# Key.net
KiCad netlist of a schematic drawn in Altium Designer
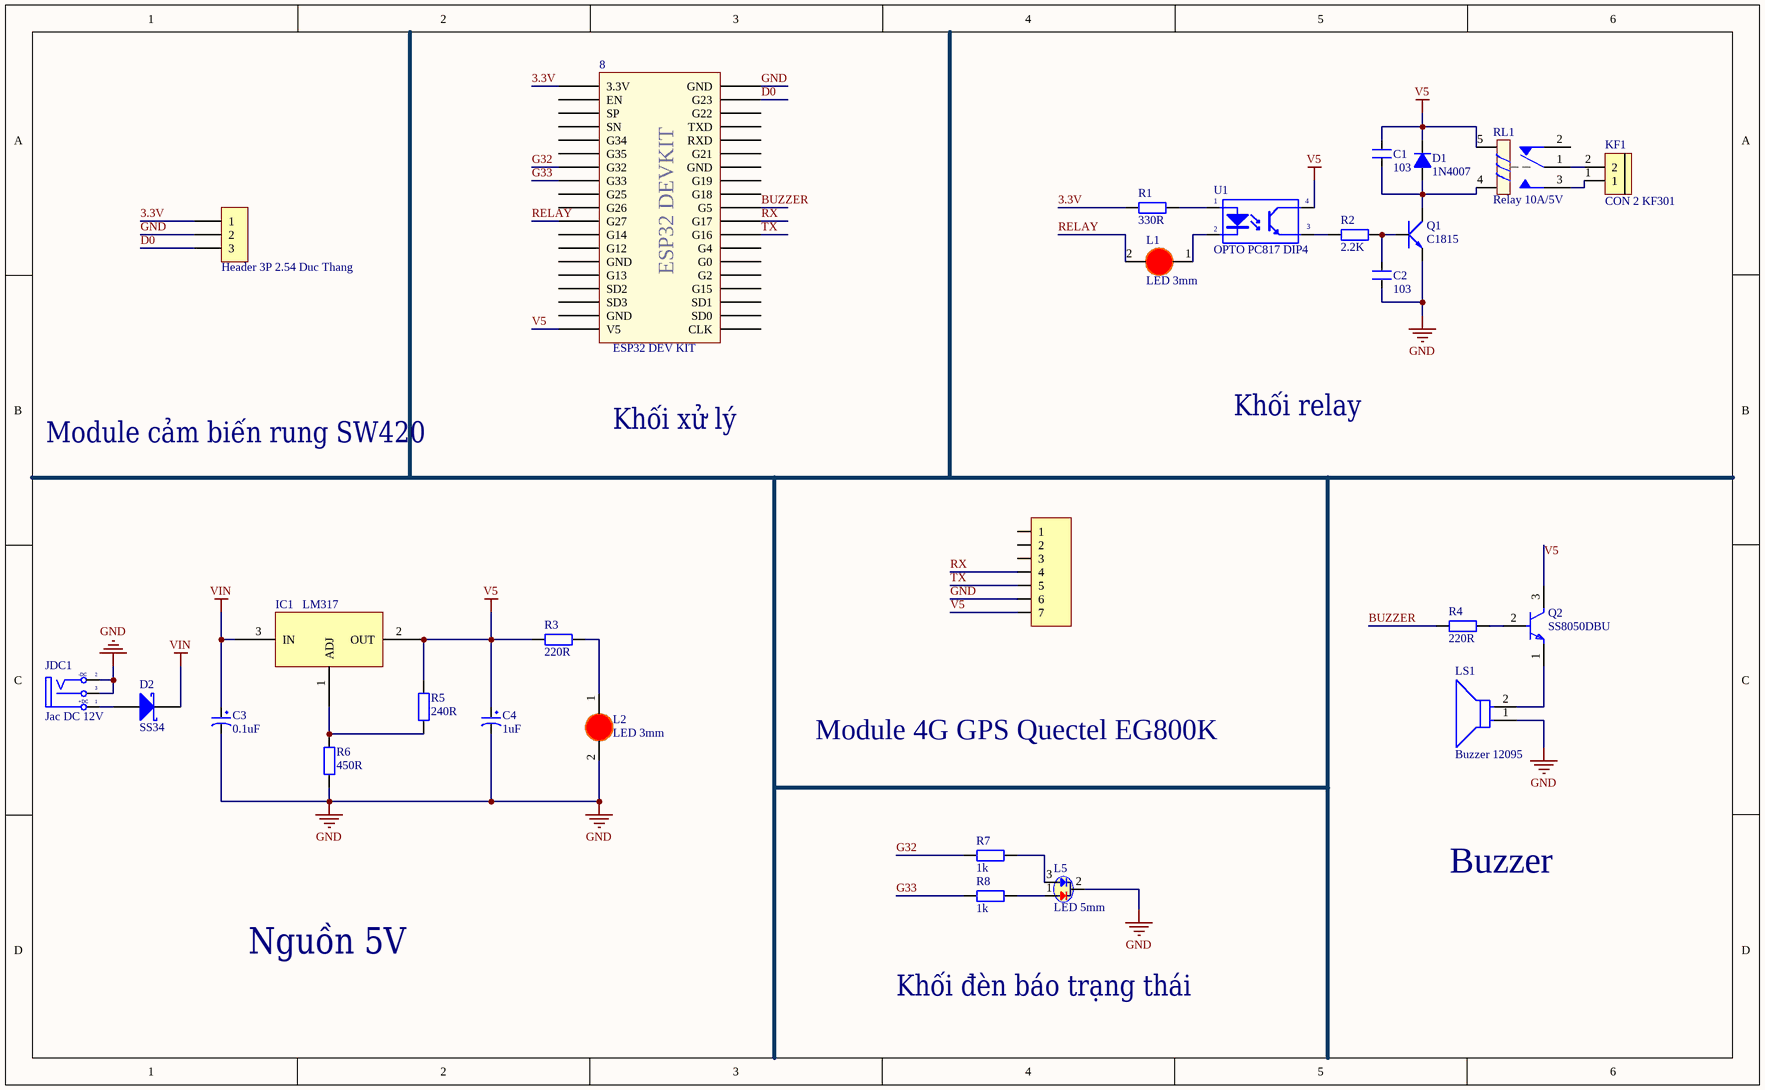
[diagram p0: Key.SchDoc]

(export (version "E")
  (design (tool "Eeschema 10.0.6"))
  (components
    (comp (ref "8")
      (value "ESP32 DEV KIT")
      (footprint "ESP32 DEVKIT")
      (libsource (lib "Altium_Lib_by_KhueNguyenCreator") (part "ESP32 DEV KIT"))
    )
    (comp (ref "C1")
      (value "103")
      (footprint "CN1.5")
      (description "Cap np 682pF => 104pF")
      (libsource (lib "syhaunguyen") (part "CN1.5"))
    )
    (comp (ref "C2")
      (value "103")
      (footprint "CN1.5")
      (description "Cap np 682pF => 104pF")
      (libsource (lib "syhaunguyen") (part "CN1.5"))
    )
    (comp (ref "C3")
      (value "0.1uF")
      (footprint "CP1/2")
      (description "Cap P  0,1uF < 22uF , 16 - 50V")
      (libsource (lib "syhaunguyen") (part "CP1"))
    )
    (comp (ref "C4")
      (value "1uF")
      (footprint "CP1/2")
      (description "Cap P  0,1uF < 22uF , 16 - 50V")
      (libsource (lib "syhaunguyen") (part "CP1"))
    )
    (comp (ref "D1")
      (value "1N4007")
      (footprint "DIODE 1A")
      (description "Cắm")
      (libsource (lib "Altium_Lib_by_KhueNguyenCreator") (part "Diode 1N4007"))
    )
    (comp (ref "D2")
      (value "SS34")
      (footprint "SS14")
      (description "Schottky Diode")
      (fields (field (name "PUBLISHER") "Altium Limited"))
      (libsource (lib "Miscellaneous Devices") (part "D Schottky"))
    )
    (comp (ref "H1")
      (value "Header 3P 2.54 Duc Thang")
      (footprint "XH2.54M-3")
      (description "Cắm")
      (libsource (lib "Altium_Lib_by_KhueNguyenCreator") (part "Header 3P 2.54 Duc Thang"))
    )
    (comp (ref "IC1")
      (value "LM317")
      (footprint "SOT223")
      (description "Dán")
      (libsource (lib "IC") (part "LM317 TO223 SMD"))
    )
    (comp (ref "JDC1")
      (value "Jac DC 12V")
      (footprint "DC-IN")
      (description "Jac DC input")
      (libsource (lib "syhaunguyen") (part "DCIN"))
    )
    (comp (ref "JP2")
      (value "~")
      (footprint "JP 1x7 CT")
      (description "Cắm")
      (libsource (lib "Altium_Lib_by_KhueNguyenCreator") (part "JP 1x7 2.54 Cai Thang"))
    )
    (comp (ref "KF1")
      (value "CON 2 KF301")
      (footprint "Con 2 KF301 5.08")
      (description "Cắm")
      (libsource (lib "Altium_Lib_by_KhueNguyenCreator") (part "CON 2 KF301"))
    )
    (comp (ref "L1")
      (value "LED 3mm")
      (footprint "LED-3MM-RED")
      (description "Cắm")
      (libsource (lib "Altium_Lib_by_KhueNguyenCreator") (part "LED 3mm Do"))
    )
    (comp (ref "L2")
      (value "LED 3mm")
      (footprint "LED-3MM-RED")
      (description "Cắm")
      (libsource (lib "Altium_Lib_by_KhueNguyenCreator") (part "LED 3mm Do"))
    )
    (comp (ref "L5")
      (value "LED 5mm")
      (footprint "LED-5MM 2 MAU")
      (description "Cắm")
      (libsource (lib "Altium_Lib_by_KhueNguyenCreator") (part "LED 5mm 2 mau Katot chung"))
    )
    (comp (ref "LS1")
      (value "Buzzer 12095")
      (footprint "FP-MCKPX-G1203A-K4056-MFG")
      (description "MAGNETIC BUZZER AND TRANSDUCER - More Details")
      (fields
        (field (name "MANUFACTURER PART NUMBER") "MCKPX-G1203A-K4056")
        (field (name "MANUFACTURER") "Multicomp Pro")
      )
      (libsource (lib "buzzer_pin7.6mm") (part "CMP-12433-000001-1"))
    )
    (comp (ref "Q1")
      (value "C1815")
      (footprint "TO92")
      (description "NPN transistor")
      (libsource (lib "Altium_Lib_by_KhueNguyenCreator") (part "Trans C1815 DIP"))
    )
    (comp (ref "Q2")
      (value "SS8050DBU")
      (footprint "FP-135AN-MFG")
      (description "SS8050DBU Bipolar (BJT) Single Transistor, NPN, 25 V, 100 MHz, 1 W, 1.5 A, 160")
      (libsource (lib "S8050_cam") (part "CMP-00278-84331634-1"))
    )
    (comp (ref "R1")
      (value "330R")
      (footprint "tro vach 1/4w")
      (description "Cắm")
      (libsource (lib "Altium_Lib_by_KhueNguyenCreator") (part "Tro Vach 1/4W 1% 330R"))
    )
    (comp (ref "R2")
      (value "2.2K")
      (footprint "tro vach 1/4w")
      (description "Cắm")
      (libsource (lib "Altium_Lib_by_KhueNguyenCreator") (part "Tro Vach 1/4W 5% 1k"))
    )
    (comp (ref "R3")
      (value "220R")
      (footprint "tro vach 1/4w")
      (description "Cắm")
      (libsource (lib "Altium_Lib_by_KhueNguyenCreator") (part "Tro Vach 1/4W 5% 220R"))
    )
    (comp (ref "R4")
      (value "220R")
      (footprint "tro vach 1/4w")
      (description "Cắm")
      (libsource (lib "Altium_Lib_by_KhueNguyenCreator") (part "Tro Vach 1/4W 5% 220R"))
    )
    (comp (ref "R5")
      (value "240R")
      (footprint "tro vach 1/4w")
      (description "Cắm")
      (libsource (lib "Altium_Lib_by_KhueNguyenCreator") (part "Tro Vach 1/4W 5% 220R"))
    )
    (comp (ref "R6")
      (value "450R")
      (footprint "tro vach 1/4w")
      (description "Cắm")
      (libsource (lib "Altium_Lib_by_KhueNguyenCreator") (part "Tro Vach 1/4W 5% 220R"))
    )
    (comp (ref "R7")
      (value "1k")
      (footprint "tro vach 1/4w")
      (description "Cắm")
      (libsource (lib "Altium_Lib_by_KhueNguyenCreator") (part "Tro Vach 1/4W 5% 220R"))
    )
    (comp (ref "R8")
      (value "1k")
      (footprint "tro vach 1/4w")
      (description "Cắm")
      (libsource (lib "Altium_Lib_by_KhueNguyenCreator") (part "Tro Vach 1/4W 5% 220R"))
    )
    (comp (ref "RL1")
      (value "Relay 10A/5V")
      (footprint "Relay 5 Chan SRD")
      (description "Relay 5 Chan")
      (libsource (lib "Altium_Lib_by_KhueNguyenCreator") (part "Relay 5 Chan SRD"))
    )
    (comp (ref "U1")
      (value "OPTO PC817 DIP4")
      (footprint "DIP4")
      (description "Single Opto")
      (libsource (lib "Altium_Lib_by_KhueNguyenCreator") (part "OPTO PC817 DIP4"))
    )
  )
  (nets
    (net (code "1") (name "/3.3V") (class "Default")
      (node (ref "8") (pin "1") (pinfunction "3.3V_1") (pintype "passive"))
      (node (ref "H1") (pin "1") (pinfunction "1_1") (pintype "passive"))
      (node (ref "R1") (pin "1") (pinfunction "1_1") (pintype "passive"))
    )
    (net (code "2") (name "/BUZZER") (class "Default")
      (node (ref "8") (pin "29") (pinfunction "G5_29") (pintype "passive"))
      (node (ref "R4") (pin "1") (pinfunction "1_1") (pintype "passive"))
    )
    (net (code "3") (name "/D0") (class "Default")
      (node (ref "8") (pin "37") (pinfunction "G23_37") (pintype "passive"))
      (node (ref "H1") (pin "3") (pinfunction "3_3") (pintype "passive"))
    )
    (net (code "4") (name "/G32") (class "Default")
      (node (ref "8") (pin "7") (pinfunction "G32_7") (pintype "passive"))
      (node (ref "R7") (pin "1") (pinfunction "1_1") (pintype "passive"))
    )
    (net (code "5") (name "/G33") (class "Default")
      (node (ref "8") (pin "8") (pinfunction "G33_8") (pintype "passive"))
      (node (ref "R8") (pin "1") (pinfunction "1_1") (pintype "passive"))
    )
    (net (code "6") (name "/RELAY") (class "Default")
      (node (ref "8") (pin "11") (pinfunction "G27_11") (pintype "passive"))
      (node (ref "L1") (pin "2") (pinfunction "K_2") (pintype "passive"))
    )
    (net (code "7") (name "/RX") (class "Default")
      (node (ref "8") (pin "28") (pinfunction "G17_28") (pintype "passive"))
      (node (ref "JP2") (pin "4") (pinfunction "4_4") (pintype "passive"))
    )
    (net (code "8") (name "/TX") (class "Default")
      (node (ref "8") (pin "27") (pinfunction "G16_27") (pintype "passive"))
      (node (ref "JP2") (pin "5") (pinfunction "5_5") (pintype "passive"))
    )
    (net (code "9") (name "GND") (class "Default")
      (node (ref "8") (pin "38") (pinfunction "GND_38") (pintype "passive"))
      (node (ref "C2") (pin "1") (pinfunction "1_1") (pintype "passive"))
      (node (ref "C3") (pin "2") (pinfunction "2_2") (pintype "passive"))
      (node (ref "C4") (pin "2") (pinfunction "2_2") (pintype "passive"))
      (node (ref "H1") (pin "2") (pinfunction "2_2") (pintype "passive"))
      (node (ref "JDC1") (pin "2") (pinfunction "TN_2") (pintype "passive"))
      (node (ref "JDC1") (pin "3") (pinfunction "S_3") (pintype "power_in"))
      (node (ref "JP2") (pin "6") (pinfunction "6_6") (pintype "passive"))
      (node (ref "L2") (pin "2") (pinfunction "K_2") (pintype "passive"))
      (node (ref "L5") (pin "2") (pinfunction "Katot_2") (pintype "passive"))
      (node (ref "LS1") (pin "1") (pinfunction "C_1") (pintype "passive"))
      (node (ref "Q1") (pin "1") (pinfunction "E_1") (pintype "passive"))
      (node (ref "R6") (pin "1") (pinfunction "1_1") (pintype "passive"))
    )
    (net (code "10") (name "Net-(D1-A)") (class "Default")
      (node (ref "C1") (pin "1") (pinfunction "1_1") (pintype "passive"))
      (node (ref "D1") (pin "1") (pinfunction "A_1") (pintype "passive"))
      (node (ref "Q1") (pin "2") (pinfunction "C_2") (pintype "passive"))
      (node (ref "RL1") (pin "4") (pinfunction "4_4") (pintype "passive"))
    )
    (net (code "11") (name "Net-(D2-A)") (class "Default")
      (node (ref "D2") (pin "1") (pinfunction "A_1") (pintype "passive"))
      (node (ref "JDC1") (pin "1") (pinfunction "T_1") (pintype "passive"))
    )
    (net (code "12") (name "Net-(IC1-ADJ)") (class "Default")
      (node (ref "IC1") (pin "1") (pinfunction "ADJ_1") (pintype "passive"))
      (node (ref "R5") (pin "1") (pinfunction "1_1") (pintype "passive"))
      (node (ref "R6") (pin "2") (pinfunction "2_2") (pintype "passive"))
    )
    (net (code "13") (name "Net-(KF1-Pad1)") (class "Default")
      (node (ref "KF1") (pin "1") (pinfunction "1_1") (pintype "passive"))
      (node (ref "RL1") (pin "3") (pinfunction "3_3") (pintype "passive"))
    )
    (net (code "14") (name "Net-(KF1-Pad2)") (class "Default")
      (node (ref "KF1") (pin "2") (pinfunction "2_2") (pintype "passive"))
      (node (ref "RL1") (pin "1") (pinfunction "1_1") (pintype "passive"))
    )
    (net (code "15") (name "Net-(L1-A)") (class "Default")
      (node (ref "L1") (pin "1") (pinfunction "A_1") (pintype "passive"))
      (node (ref "U1") (pin "2") (pinfunction "K_2") (pintype "passive"))
    )
    (net (code "16") (name "Net-(L2-A)") (class "Default")
      (node (ref "L2") (pin "1") (pinfunction "A_1") (pintype "passive"))
      (node (ref "R3") (pin "2") (pinfunction "2_2") (pintype "passive"))
    )
    (net (code "17") (name "Net-(L5-D)") (class "Default")
      (node (ref "L5") (pin "1") (pinfunction "D_1") (pintype "passive"))
      (node (ref "R8") (pin "2") (pinfunction "2_2") (pintype "passive"))
    )
    (net (code "18") (name "Net-(L5-X)") (class "Default")
      (node (ref "L5") (pin "3") (pinfunction "X_3") (pintype "passive"))
      (node (ref "R7") (pin "2") (pinfunction "2_2") (pintype "passive"))
    )
    (net (code "19") (name "Net-(LS1-A)") (class "Default")
      (node (ref "LS1") (pin "2") (pinfunction "A_2") (pintype "passive"))
      (node (ref "Q2") (pin "1") (pinfunction "E_1") (pintype "passive"))
    )
    (net (code "20") (name "Net-(Q1-B)") (class "Default")
      (node (ref "C2") (pin "2") (pinfunction "2_2") (pintype "passive"))
      (node (ref "Q1") (pin "3") (pinfunction "B_3") (pintype "passive"))
      (node (ref "R2") (pin "2") (pinfunction "2_2") (pintype "passive"))
    )
    (net (code "21") (name "Net-(Q2-B)") (class "Default")
      (node (ref "Q2") (pin "2") (pinfunction "B_2") (pintype "passive"))
      (node (ref "R4") (pin "2") (pinfunction "2_2") (pintype "passive"))
    )
    (net (code "22") (name "Net-(U1-A)") (class "Default")
      (node (ref "R1") (pin "2") (pinfunction "2_2") (pintype "passive"))
      (node (ref "U1") (pin "1") (pinfunction "A_1") (pintype "passive"))
    )
    (net (code "23") (name "Net-(U1-E)") (class "Default")
      (node (ref "R2") (pin "1") (pinfunction "1_1") (pintype "passive"))
      (node (ref "U1") (pin "3") (pinfunction "E_3") (pintype "passive"))
    )
    (net (code "24") (name "V5") (class "Default")
      (node (ref "8") (pin "19") (pinfunction "V5_19") (pintype "passive"))
      (node (ref "C1") (pin "2") (pinfunction "2_2") (pintype "passive"))
      (node (ref "C4") (pin "1") (pinfunction "1_1") (pintype "passive"))
      (node (ref "D1") (pin "2") (pinfunction "K_2") (pintype "passive"))
      (node (ref "IC1") (pin "2") (pinfunction "OUT_2") (pintype "passive"))
      (node (ref "JP2") (pin "7") (pinfunction "7_7") (pintype "passive"))
      (node (ref "Q2") (pin "3") (pinfunction "C_3") (pintype "passive"))
      (node (ref "R3") (pin "1") (pinfunction "1_1") (pintype "passive"))
      (node (ref "R5") (pin "2") (pinfunction "2_2") (pintype "passive"))
      (node (ref "RL1") (pin "5") (pinfunction "5_5") (pintype "passive"))
      (node (ref "U1") (pin "4") (pinfunction "C_4") (pintype "passive"))
    )
    (net (code "25") (name "VIN") (class "Default")
      (node (ref "C3") (pin "1") (pinfunction "1_1") (pintype "passive"))
      (node (ref "D2") (pin "2") (pinfunction "K_2") (pintype "passive"))
      (node (ref "IC1") (pin "3") (pinfunction "IN_3") (pintype "passive"))
    )
    (net (code "26") (name "unconnected-(8-CLK-Pad20)") (class "Default")
      (node (ref "8") (pin "20") (pinfunction "CLK_20") (pintype "passive"))
    )
    (net (code "27") (name "unconnected-(8-EN-Pad2)") (class "Default")
      (node (ref "8") (pin "2") (pinfunction "EN_2") (pintype "passive"))
    )
    (net (code "28") (name "unconnected-(8-G0-Pad25)") (class "Default")
      (node (ref "8") (pin "25") (pinfunction "G0_25") (pintype "passive"))
    )
    (net (code "29") (name "unconnected-(8-G2-Pad24)") (class "Default")
      (node (ref "8") (pin "24") (pinfunction "G2_24") (pintype "passive"))
    )
    (net (code "30") (name "unconnected-(8-G4-Pad26)") (class "Default")
      (node (ref "8") (pin "26") (pinfunction "G4_26") (pintype "passive"))
    )
    (net (code "31") (name "unconnected-(8-G12-Pad13)") (class "Default")
      (node (ref "8") (pin "13") (pinfunction "G12_13") (pintype "passive"))
    )
    (net (code "32") (name "unconnected-(8-G13-Pad15)") (class "Default")
      (node (ref "8") (pin "15") (pinfunction "G13_15") (pintype "passive"))
    )
    (net (code "33") (name "unconnected-(8-G14-Pad12)") (class "Default")
      (node (ref "8") (pin "12") (pinfunction "G14_12") (pintype "passive"))
    )
    (net (code "34") (name "unconnected-(8-G15-Pad23)") (class "Default")
      (node (ref "8") (pin "23") (pinfunction "G15_23") (pintype "passive"))
    )
    (net (code "35") (name "unconnected-(8-G18-Pad30)") (class "Default")
      (node (ref "8") (pin "30") (pinfunction "G18_30") (pintype "passive"))
    )
    (net (code "36") (name "unconnected-(8-G19-Pad31)") (class "Default")
      (node (ref "8") (pin "31") (pinfunction "G19_31") (pintype "passive"))
    )
    (net (code "37") (name "unconnected-(8-G21-Pad33)") (class "Default")
      (node (ref "8") (pin "33") (pinfunction "G21_33") (pintype "passive"))
    )
    (net (code "38") (name "unconnected-(8-G22-Pad36)") (class "Default")
      (node (ref "8") (pin "36") (pinfunction "G22_36") (pintype "passive"))
    )
    (net (code "39") (name "unconnected-(8-G25-Pad9)") (class "Default")
      (node (ref "8") (pin "9") (pinfunction "G25_9") (pintype "passive"))
    )
    (net (code "40") (name "unconnected-(8-G26-Pad10)") (class "Default")
      (node (ref "8") (pin "10") (pinfunction "G26_10") (pintype "passive"))
    )
    (net (code "41") (name "unconnected-(8-G34-Pad5)") (class "Default")
      (node (ref "8") (pin "5") (pinfunction "G34_5") (pintype "passive"))
    )
    (net (code "42") (name "unconnected-(8-G35-Pad6)") (class "Default")
      (node (ref "8") (pin "6") (pinfunction "G35_6") (pintype "passive"))
    )
    (net (code "43") (name "unconnected-(8-GND-Pad14)") (class "Default")
      (node (ref "8") (pin "14") (pinfunction "GND_14") (pintype "passive"))
    )
    (net (code "44") (name "unconnected-(8-GND-Pad18)") (class "Default")
      (node (ref "8") (pin "18") (pinfunction "GND_18") (pintype "passive"))
    )
    (net (code "45") (name "unconnected-(8-GND-Pad32)") (class "Default")
      (node (ref "8") (pin "32") (pinfunction "GND_32") (pintype "passive"))
    )
    (net (code "46") (name "unconnected-(8-RXD-Pad34)") (class "Default")
      (node (ref "8") (pin "34") (pinfunction "RXD_34") (pintype "passive"))
    )
    (net (code "47") (name "unconnected-(8-SD0-Pad21)") (class "Default")
      (node (ref "8") (pin "21") (pinfunction "SD0_21") (pintype "passive"))
    )
    (net (code "48") (name "unconnected-(8-SD1-Pad22)") (class "Default")
      (node (ref "8") (pin "22") (pinfunction "SD1_22") (pintype "passive"))
    )
    (net (code "49") (name "unconnected-(8-SD2-Pad16)") (class "Default")
      (node (ref "8") (pin "16") (pinfunction "SD2_16") (pintype "passive"))
    )
    (net (code "50") (name "unconnected-(8-SD3-Pad17)") (class "Default")
      (node (ref "8") (pin "17") (pinfunction "SD3_17") (pintype "passive"))
    )
    (net (code "51") (name "unconnected-(8-SN-Pad4)") (class "Default")
      (node (ref "8") (pin "4") (pinfunction "SN_4") (pintype "passive"))
    )
    (net (code "52") (name "unconnected-(8-SP-Pad3)") (class "Default")
      (node (ref "8") (pin "3") (pinfunction "SP_3") (pintype "passive"))
    )
    (net (code "53") (name "unconnected-(8-TXD-Pad35)") (class "Default")
      (node (ref "8") (pin "35") (pinfunction "TXD_35") (pintype "passive"))
    )
    (net (code "54") (name "unconnected-(JP2-Pad1)") (class "Default")
      (node (ref "JP2") (pin "1") (pinfunction "1_1") (pintype "passive"))
    )
    (net (code "55") (name "unconnected-(JP2-Pad2)") (class "Default")
      (node (ref "JP2") (pin "2") (pinfunction "2_2") (pintype "passive"))
    )
    (net (code "56") (name "unconnected-(JP2-Pad3)") (class "Default")
      (node (ref "JP2") (pin "3") (pinfunction "3_3") (pintype "passive"))
    )
    (net (code "57") (name "unconnected-(RL1-Pad2)") (class "Default")
      (node (ref "RL1") (pin "2") (pinfunction "2_2") (pintype "passive"))
    )
  )
)
